# SmartChess_SCH.net
KiCad netlist of a schematic drawn in Altium Designer
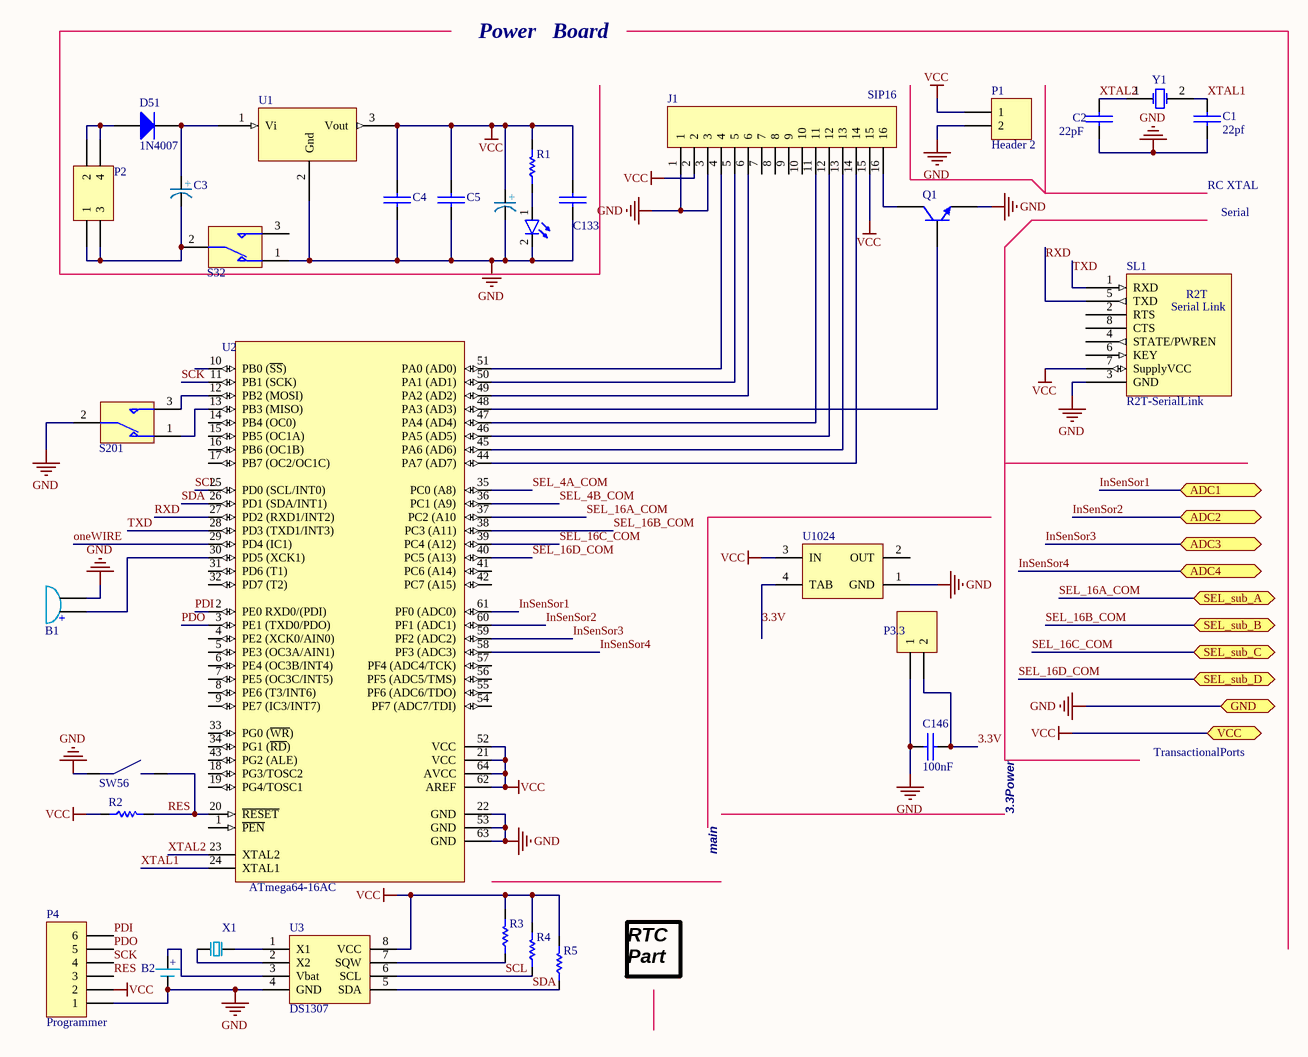
[diagram p0: SmartChess_SCH.SchDoc]

(export (version "E")
  (design (tool "Eeschema 10.0.6"))
  (components
    (comp (ref "B1")
      (value "Buzzer")
      (footprint "Buzzer")
      (fields (field (name "DESIGNER") "Hamed Jafarzadeh"))
      (libsource (lib "R2T Team Library") (part "Buzzer"))
    )
    (comp (ref "B2") (value "BAT") (footprint "BAT_H") (libsource (lib "My_lib_new") (part "BAT")))
    (comp (ref "C1")
      (value "22pf")
      (footprint "SMD_CAP_1206")
      (description "Bipolar Capacitor")
      (fields (field (name "VOLTAGE") "100V") (field (name "DESIGNER") "Saeid Jorablo"))
      (libsource (lib "My Library") (part "Cap-Bipolar"))
    )
    (comp (ref "C2")
      (value "22pF")
      (footprint "SMD_CAP_1206")
      (description "Bipolar Capacitor")
      (fields (field (name "VOLTAGE") "100V") (field (name "DESIGNER") "Saeid Jorablo"))
      (libsource (lib "My Library") (part "Cap-Bipolar"))
    )
    (comp (ref "C3")
      (value "Capacitor Polarized")
      (footprint "Electrolytic Capacitor SMD Dia-8")
      (fields (field (name "DESIGNER") "Hamed Jafarzadeh ( R2T )"))
      (libsource (lib "R2T Team Library") (part "Capacitor Polarized"))
    )
    (comp (ref "C4")
      (value "100nF")
      (footprint "SMD_CAP_1206")
      (description "Bipolar Capacitor")
      (fields (field (name "VOLTAGE") "100V") (field (name "DESIGNER") "Saeid Jorablo"))
      (libsource (lib "My Library") (part "Cap-Bipolar"))
    )
    (comp (ref "C5")
      (value "300nf")
      (footprint "SMD_CAP_1206")
      (description "Bipolar Capacitor")
      (fields (field (name "VOLTAGE") "100V") (field (name "DESIGNER") "Saeid Jorablo"))
      (libsource (lib "My Library") (part "Cap-Bipolar"))
    )
    (comp (ref "C9")
      (value "Capacitor Polarized")
      (footprint "Electrolytic Capacitor SMD Dia-8")
      (fields (field (name "DESIGNER") "Hamed Jafarzadeh ( R2T )"))
      (libsource (lib "R2T Team Library") (part "Capacitor Polarized"))
    )
    (comp (ref "C133")
      (value "100pF")
      (footprint "SMD_CAP_1206")
      (description "Bipolar Capacitor")
      (fields (field (name "VOLTAGE") "100V") (field (name "DESIGNER") "Saeid Jorablo"))
      (libsource (lib "My Library") (part "Cap-Bipolar"))
    )
    (comp (ref "C146")
      (value "100nF")
      (footprint "SMD_CAP_1206")
      (description "Bipolar Capacitor")
      (fields (field (name "VOLTAGE") "100V") (field (name "DESIGNER") "Saeid Jorablo"))
      (libsource (lib "My Library") (part "Cap-Bipolar"))
    )
    (comp (ref "D51")
      (value "1N4007")
      (footprint "My_DO-41")
      (description "1 Amp Diode")
      (libsource (lib "Mylib") (part "1N4007"))
    )
    (comp (ref "J1") (value "SIP16") (footprint "SIP16") (libsource (lib "My_lib_new") (part "SIP16")))
    (comp (ref "LED1")
      (value "Red")
      (footprint "LED SMD 1206")
      (description "LED")
      (fields (field (name "DESIGNER") "Saeid Jorablo"))
      (libsource (lib "My Library") (part "LED"))
    )
    (comp (ref "P1")
      (value "Header 2")
      (footprint "HDR1X2")
      (description "Header, 2-Pin")
      (fields (field (name "PUBLISHER") "Altium Limited"))
      (libsource (lib "") (part "Header 2_1"))
    )
    (comp (ref "P2")
      (value "Header 2X2")
      (footprint "HDR2X2")
      (description "Header, 2-Pin, Dual row")
      (fields (field (name "PUBLISHER") "Altium Limited"))
      (libsource (lib "Miscellaneous Connectors") (part "Header 2X2"))
    )
    (comp (ref "P3.3")
      (value "Header 2")
      (footprint "HDR1X2")
      (description "Header, 2-Pin")
      (fields (field (name "PUBLISHER") "Altium Limited"))
      (libsource (lib "Miscellaneous Connectors") (part "Header 2"))
    )
    (comp (ref "P4")
      (value "Programmer")
      (footprint "HDR1X6")
      (description "Header, 6-Pin")
      (fields (field (name "PUBLISHER") "Altium Limited"))
      (libsource (lib "Miscellaneous Connectors") (part "Header 6"))
    )
    (comp (ref "Q1")
      (value "C945")
      (footprint "C945")
      (description "NPN Transistor")
      (fields (field (name "DESIGNER") "Saeid Jorablo"))
      (libsource (lib "My Library") (part "C945"))
    )
    (comp (ref "R1")
      (value "330")
      (footprint "RES 0805 (2012X06L)")
      (description "Resistor")
      (fields (field (name "TOLERANCE") "5%") (field (name "POWER") "1/8 W"))
      (libsource (lib "My Library") (part "Resistor"))
    )
    (comp (ref "R2")
      (value "1K")
      (footprint "RES 0805 (2012X06L)")
      (description "Resistor")
      (fields (field (name "TOLERANCE") "5%") (field (name "POWER") "1/8 W"))
      (libsource (lib "My Library") (part "Resistor"))
    )
    (comp (ref "R3")
      (value "1K")
      (footprint "RES 0805 (2012X06L)")
      (description "Resistor")
      (fields (field (name "TOLERANCE") "5%") (field (name "POWER") "1/8 W"))
      (libsource (lib "My Library") (part "Resistor"))
    )
    (comp (ref "R4")
      (value "1K")
      (footprint "RES 0805 (2012X06L)")
      (description "Resistor")
      (fields (field (name "TOLERANCE") "5%") (field (name "POWER") "1/8 W"))
      (libsource (lib "My Library") (part "Resistor"))
    )
    (comp (ref "R5")
      (value "1K")
      (footprint "RES 0805 (2012X06L)")
      (description "Resistor")
      (fields (field (name "TOLERANCE") "5%") (field (name "POWER") "1/8 W"))
      (libsource (lib "My Library") (part "Resistor"))
    )
    (comp (ref "S32")
      (value "Switch SPDT_Subminiator")
      (footprint "SPDT Subminiator")
      (description "Subminiator SPDT Switch")
      (libsource (lib "My Library") (part "Switch SPDT_Subminiator"))
    )
    (comp (ref "S201")
      (value "Switch SPDT_Subminiator")
      (footprint "SPDT Subminiator")
      (description "Subminiator SPDT Switch")
      (libsource (lib "My Library") (part "Switch SPDT_Subminiator"))
    )
    (comp (ref "SL1")
      (value "R2T-SerialLink")
      (footprint "Bluetooth Serial")
      (fields (field (name "DESIGNER") "Hamed Jafarzadeh-WWW.R2T.IR"))
      (libsource (lib "R2T Team Library") (part "R2T-SerialLink"))
    )
    (comp (ref "SW56") (value "SWITCH") (footprint "SWITCH") (libsource (lib "SPLib") (part "SWITCH")))
    (comp (ref "U1")
      (value "78M05")
      (footprint "DPAK228P972X240-3N")
      (libsource (lib "R2T Team Library") (part "78M05"))
    )
    (comp (ref "U2")
      (value "ATmega64-16AC")
      (footprint "64A_N")
      (description "8-Bit AVR Microcontroller with 64K Bytes of In-System Programmable Flash Memory")
      (fields (field (name "PUBLISHER") "Altium Limited"))
      (libsource (lib "Atmel Microcontroller 8-Bit AVR") (part "ATmega64-16AC"))
    )
    (comp (ref "U3") (value "DS1307") (footprint "DIP8") (libsource (lib "My_lib_new") (part "DS1307")))
    (comp (ref "U1024")
      (value "LM1117IMP-x.x")
      (footprint "MP04A_N")
      (description "x.x Volt, 800mA Low-Dropout Linear Regulator, 4-pin SOT-223")
      (fields
        (field (name "PARTNUMBER") "LM1117IMP-3.3")
        (field (name "MANUFACTURER") "National Semiconductor")
        (field (name "PUBLISHER") "Altium Limited")
      )
      (libsource (lib "My Library") (part "LM1117IMP-x.x"))
    )
    (comp (ref "X1") (value "XTAL") (footprint "XTAL2") (libsource (lib "My_lib_new") (part "XTAL")))
    (comp (ref "Y1")
      (value "8Mhz")
      (footprint "Crystal SMD")
      (description "XTAL Crystal")
      (libsource (lib "My Library") (part "XTAL"))
    )
  )
  (nets
    (net (code "1") (name "/3.3V") (class "Default")
      (node (ref "C146") (pin "2") (pinfunction "-_2") (pintype "passive"))
      (node (ref "P3.3") (pin "2") (pinfunction "2_2") (pintype "passive"))
      (node (ref "U1024") (pin "4") (pinfunction "TAB_4") (pintype "power_in"))
    )
    (net (code "2") (name "/InSenSor1") (class "Default")
      (node (ref "U2") (pin "61") (pinfunction "PF0_(ADC0)_61") (pintype "bidirectional"))
    )
    (net (code "3") (name "/InSenSor2") (class "Default")
      (node (ref "U2") (pin "60") (pinfunction "PF1_(ADC1)_60") (pintype "bidirectional"))
    )
    (net (code "4") (name "/InSenSor3") (class "Default")
      (node (ref "U2") (pin "59") (pinfunction "PF2_(ADC2)_59") (pintype "bidirectional"))
    )
    (net (code "5") (name "/InSenSor4") (class "Default")
      (node (ref "U2") (pin "58") (pinfunction "PF3_(ADC3)_58") (pintype "bidirectional"))
    )
    (net (code "6") (name "/PDI") (class "Default")
      (node (ref "P4") (pin "6") (pinfunction "6_6") (pintype "passive"))
      (node (ref "U2") (pin "2") (pinfunction "PE0_RXD0/(PDI)_2") (pintype "bidirectional"))
    )
    (net (code "7") (name "/PDO") (class "Default")
      (node (ref "P4") (pin "5") (pinfunction "5_5") (pintype "passive"))
      (node (ref "U2") (pin "3") (pinfunction "PE1_(TXD0/PDO)_3") (pintype "bidirectional"))
    )
    (net (code "8") (name "/RES") (class "Default")
      (node (ref "P4") (pin "3") (pinfunction "3_3") (pintype "passive"))
      (node (ref "R2") (pin "2") (pinfunction "2_2") (pintype "passive"))
      (node (ref "SW56") (pin "2") (pinfunction "2_2") (pintype "passive"))
      (node (ref "U2") (pin "20") (pinfunction "~{RESET}_20") (pintype "input"))
    )
    (net (code "9") (name "/RXD") (class "Default")
      (node (ref "SL1") (pin "5") (pinfunction "TXD_5") (pintype "output"))
      (node (ref "U2") (pin "27") (pinfunction "PD2_(RXD1/INT2)_27") (pintype "bidirectional"))
    )
    (net (code "10") (name "/SCK") (class "Default")
      (node (ref "P4") (pin "4") (pinfunction "4_4") (pintype "passive"))
      (node (ref "U2") (pin "11") (pinfunction "PB1_(SCK)_11") (pintype "bidirectional"))
    )
    (net (code "11") (name "/SCL") (class "Default")
      (node (ref "R4") (pin "1") (pinfunction "1_1") (pintype "passive"))
      (node (ref "U2") (pin "25") (pinfunction "PD0_(SCL/INT0)_25") (pintype "bidirectional"))
      (node (ref "U3") (pin "6") (pinfunction "SCL_6") (pintype "passive"))
    )
    (net (code "12") (name "/SDA") (class "Default")
      (node (ref "R5") (pin "1") (pinfunction "1_1") (pintype "passive"))
      (node (ref "U2") (pin "26") (pinfunction "PD1_(SDA/INT1)_26") (pintype "bidirectional"))
      (node (ref "U3") (pin "5") (pinfunction "SDA_5") (pintype "passive"))
    )
    (net (code "13") (name "/SEL_4A_COM") (class "Default")
      (node (ref "U2") (pin "35") (pinfunction "PC0_(A8)_35") (pintype "bidirectional"))
    )
    (net (code "14") (name "/SEL_4B_COM") (class "Default")
      (node (ref "U2") (pin "36") (pinfunction "PC1_(A9)_36") (pintype "bidirectional"))
    )
    (net (code "15") (name "/SEL_16A_COM") (class "Default")
      (node (ref "U2") (pin "37") (pinfunction "PC2_(A10_37") (pintype "bidirectional"))
    )
    (net (code "16") (name "/SEL_16B_COM") (class "Default")
      (node (ref "U2") (pin "38") (pinfunction "PC3_(A11)_38") (pintype "bidirectional"))
    )
    (net (code "17") (name "/SEL_16C_COM") (class "Default")
      (node (ref "U2") (pin "39") (pinfunction "PC4_(A12)_39") (pintype "bidirectional"))
    )
    (net (code "18") (name "/SEL_16D_COM") (class "Default")
      (node (ref "U2") (pin "40") (pinfunction "PC5_(A13)_40") (pintype "bidirectional"))
    )
    (net (code "19") (name "/TXD") (class "Default")
      (node (ref "SL1") (pin "1") (pinfunction "RXD_1") (pintype "input"))
      (node (ref "U2") (pin "28") (pinfunction "PD3_(TXD1/INT3)_28") (pintype "bidirectional"))
    )
    (net (code "20") (name "/XTAL1") (class "Default")
      (node (ref "C1") (pin "1") (pinfunction "+_1") (pintype "passive"))
      (node (ref "U2") (pin "24") (pinfunction "XTAL1_24") (pintype "passive"))
      (node (ref "Y1") (pin "2") (pinfunction "OSC2_2") (pintype "passive"))
    )
    (net (code "21") (name "/XTAL2") (class "Default")
      (node (ref "C2") (pin "1") (pinfunction "+_1") (pintype "passive"))
      (node (ref "U2") (pin "23") (pinfunction "XTAL2_23") (pintype "passive"))
      (node (ref "Y1") (pin "1") (pinfunction "OSC1_1") (pintype "passive"))
    )
    (net (code "22") (name "/oneWIRE") (class "Default")
      (node (ref "U2") (pin "29") (pinfunction "PD4_(IC1)_29") (pintype "bidirectional"))
    )
    (net (code "23") (name "GND") (class "Default")
      (node (ref "B1") (pin "2") (pinfunction "GND_2") (pintype "passive"))
      (node (ref "B2") (pin "2") (pintype "passive"))
      (node (ref "C1") (pin "2") (pinfunction "-_2") (pintype "passive"))
      (node (ref "C133") (pin "2") (pinfunction "-_2") (pintype "passive"))
      (node (ref "C146") (pin "1") (pinfunction "+_1") (pintype "passive"))
      (node (ref "C2") (pin "2") (pinfunction "-_2") (pintype "passive"))
      (node (ref "C4") (pin "2") (pinfunction "-_2") (pintype "passive"))
      (node (ref "C5") (pin "2") (pinfunction "-_2") (pintype "passive"))
      (node (ref "C9") (pin "2") (pintype "passive"))
      (node (ref "J1") (pin "1") (pinfunction "1_1") (pintype "passive"))
      (node (ref "J1") (pin "3") (pinfunction "3_3") (pintype "passive"))
      (node (ref "LED1") (pin "2") (pinfunction "K_2") (pintype "passive"))
      (node (ref "P1") (pin "2") (pinfunction "2_2") (pintype "passive"))
      (node (ref "P3.3") (pin "1") (pinfunction "1_1") (pintype "passive"))
      (node (ref "P4") (pin "1") (pinfunction "1_1") (pintype "passive"))
      (node (ref "Q1") (pin "1") (pinfunction "E_1") (pintype "passive"))
      (node (ref "S201") (pin "2") (pinfunction "2_2") (pintype "passive"))
      (node (ref "S32") (pin "1") (pinfunction "1_1") (pintype "passive"))
      (node (ref "SL1") (pin "3") (pinfunction "GND_3") (pintype "passive"))
      (node (ref "SW56") (pin "1") (pinfunction "1_1") (pintype "passive"))
      (node (ref "U1") (pin "2") (pinfunction "Gnd_2") (pintype "passive"))
      (node (ref "U1024") (pin "1") (pinfunction "GND_1") (pintype "power_in"))
      (node (ref "U2") (pin "22") (pinfunction "GND_22") (pintype "power_in"))
      (node (ref "U2") (pin "53") (pinfunction "GND_53") (pintype "power_in"))
      (node (ref "U2") (pin "63") (pinfunction "GND_63") (pintype "power_in"))
      (node (ref "U3") (pin "4") (pinfunction "GND_4") (pintype "passive"))
    )
    (net (code "24") (name "Net-(B1-VCC)") (class "Default")
      (node (ref "B1") (pin "1") (pinfunction "VCC_1") (pintype "passive"))
      (node (ref "U2") (pin "30") (pinfunction "PD5_(XCK1)_30") (pintype "bidirectional"))
    )
    (net (code "25") (name "Net-(C3-Pad2)") (class "Default")
      (node (ref "C3") (pin "2") (pintype "passive"))
      (node (ref "P2") (pin "1") (pinfunction "1_1") (pintype "passive"))
      (node (ref "P2") (pin "3") (pinfunction "3_3") (pintype "passive"))
      (node (ref "S32") (pin "2") (pinfunction "2_2") (pintype "passive"))
    )
    (net (code "26") (name "Net-(D51-PadA)") (class "Default")
      (node (ref "D51") (pin "A") (pinfunction "A_A") (pintype "passive"))
      (node (ref "P2") (pin "2") (pinfunction "2_2") (pintype "passive"))
      (node (ref "P2") (pin "4") (pinfunction "4_4") (pintype "passive"))
    )
    (net (code "27") (name "Net-(LED1-A)") (class "Default")
      (node (ref "LED1") (pin "1") (pinfunction "A_1") (pintype "passive"))
      (node (ref "R1") (pin "1") (pinfunction "1_1") (pintype "passive"))
    )
    (net (code "28") (name "Net-(Q1-B)") (class "Default")
      (node (ref "Q1") (pin "3") (pinfunction "B_3") (pintype "passive"))
      (node (ref "U2") (pin "48") (pinfunction "PA3_(AD3)_48") (pintype "bidirectional"))
    )
    (net (code "29") (name "Net-(Q1-C)") (class "Default")
      (node (ref "J1") (pin "16") (pinfunction "16_16") (pintype "passive"))
      (node (ref "Q1") (pin "2") (pinfunction "C_2") (pintype "passive"))
    )
    (net (code "30") (name "Net-(U1-Vi)") (class "Default")
      (node (ref "C3") (pin "1") (pintype "passive"))
      (node (ref "D51") (pin "K") (pinfunction "K_K") (pintype "passive"))
      (node (ref "U1") (pin "1") (pinfunction "Vi_1") (pintype "input"))
    )
    (net (code "31") (name "Net-(U2-PA0_(AD0))") (class "Default")
      (node (ref "J1") (pin "4") (pinfunction "4_4") (pintype "passive"))
      (node (ref "U2") (pin "51") (pinfunction "PA0_(AD0)_51") (pintype "bidirectional"))
    )
    (net (code "32") (name "Net-(U2-PA1_(AD1))") (class "Default")
      (node (ref "J1") (pin "5") (pinfunction "5_5") (pintype "passive"))
      (node (ref "U2") (pin "50") (pinfunction "PA1_(AD1)_50") (pintype "bidirectional"))
    )
    (net (code "33") (name "Net-(U2-PA2_(AD2))") (class "Default")
      (node (ref "J1") (pin "6") (pinfunction "6_6") (pintype "passive"))
      (node (ref "U2") (pin "49") (pinfunction "PA2_(AD2)_49") (pintype "bidirectional"))
    )
    (net (code "34") (name "Net-(U2-PA4_(AD4))") (class "Default")
      (node (ref "J1") (pin "11") (pinfunction "11_11") (pintype "passive"))
      (node (ref "U2") (pin "47") (pinfunction "PA4_(AD4)_47") (pintype "bidirectional"))
    )
    (net (code "35") (name "Net-(U2-PA5_(AD5))") (class "Default")
      (node (ref "J1") (pin "12") (pinfunction "12_12") (pintype "passive"))
      (node (ref "U2") (pin "46") (pinfunction "PA5_(AD5)_46") (pintype "bidirectional"))
    )
    (net (code "36") (name "Net-(U2-PA6_(AD6))") (class "Default")
      (node (ref "J1") (pin "13") (pinfunction "13_13") (pintype "passive"))
      (node (ref "U2") (pin "45") (pinfunction "PA6_(AD6)_45") (pintype "bidirectional"))
    )
    (net (code "37") (name "Net-(U2-PA7_(AD7))") (class "Default")
      (node (ref "J1") (pin "14") (pinfunction "14_14") (pintype "passive"))
      (node (ref "U2") (pin "44") (pinfunction "PA7_(AD7)_44") (pintype "bidirectional"))
    )
    (net (code "38") (name "Net-(U2-PB2_(MOSI))") (class "Default")
      (node (ref "S201") (pin "3") (pinfunction "3_3") (pintype "passive"))
      (node (ref "U2") (pin "12") (pinfunction "PB2_(MOSI)_12") (pintype "bidirectional"))
    )
    (net (code "39") (name "Net-(U2-PB3_(MISO))") (class "Default")
      (node (ref "S201") (pin "1") (pinfunction "1_1") (pintype "passive"))
      (node (ref "U2") (pin "13") (pinfunction "PB3_(MISO)_13") (pintype "bidirectional"))
    )
    (net (code "40") (name "Net-(U3-SQW)") (class "Default")
      (node (ref "R3") (pin "1") (pinfunction "1_1") (pintype "passive"))
      (node (ref "U3") (pin "7") (pinfunction "SQW_7") (pintype "passive"))
    )
    (net (code "41") (name "Net-(U3-Vbat)") (class "Default")
      (node (ref "B2") (pin "1") (pintype "passive"))
      (node (ref "U3") (pin "3") (pinfunction "Vbat_3") (pintype "passive"))
    )
    (net (code "42") (name "Net-(U3-X1)") (class "Default")
      (node (ref "U3") (pin "1") (pinfunction "X1_1") (pintype "passive"))
      (node (ref "X1") (pin "1") (pintype "passive"))
    )
    (net (code "43") (name "Net-(U3-X2)") (class "Default")
      (node (ref "U3") (pin "2") (pinfunction "X2_2") (pintype "passive"))
      (node (ref "X1") (pin "2") (pintype "passive"))
    )
    (net (code "44") (name "VCC") (class "Default")
      (node (ref "C133") (pin "1") (pinfunction "+_1") (pintype "passive"))
      (node (ref "C4") (pin "1") (pinfunction "+_1") (pintype "passive"))
      (node (ref "C5") (pin "1") (pinfunction "+_1") (pintype "passive"))
      (node (ref "C9") (pin "1") (pintype "passive"))
      (node (ref "J1") (pin "15") (pinfunction "15_15") (pintype "passive"))
      (node (ref "J1") (pin "2") (pinfunction "2_2") (pintype "passive"))
      (node (ref "P1") (pin "1") (pinfunction "1_1") (pintype "passive"))
      (node (ref "P4") (pin "2") (pinfunction "2_2") (pintype "passive"))
      (node (ref "R1") (pin "2") (pinfunction "2_2") (pintype "passive"))
      (node (ref "R2") (pin "1") (pinfunction "1_1") (pintype "passive"))
      (node (ref "R3") (pin "2") (pinfunction "2_2") (pintype "passive"))
      (node (ref "R4") (pin "2") (pinfunction "2_2") (pintype "passive"))
      (node (ref "R5") (pin "2") (pinfunction "2_2") (pintype "passive"))
      (node (ref "SL1") (pin "7") (pinfunction "SupplyVCC_7") (pintype "bidirectional"))
      (node (ref "U1") (pin "3") (pinfunction "Vout_3") (pintype "output"))
      (node (ref "U1024") (pin "3") (pinfunction "IN_3") (pintype "power_in"))
      (node (ref "U2") (pin "21") (pinfunction "VCC_21") (pintype "power_in"))
      (node (ref "U2") (pin "52") (pinfunction "VCC_52") (pintype "power_in"))
      (node (ref "U2") (pin "62") (pinfunction "AREF_62") (pintype "passive"))
      (node (ref "U2") (pin "64") (pinfunction "AVCC_64") (pintype "power_in"))
      (node (ref "U3") (pin "8") (pinfunction "VCC_8") (pintype "passive"))
    )
    (net (code "45") (name "unconnected-(J1-Pad7)") (class "Default")
      (node (ref "J1") (pin "7") (pinfunction "7_7") (pintype "passive"))
    )
    (net (code "46") (name "unconnected-(J1-Pad8)") (class "Default")
      (node (ref "J1") (pin "8") (pinfunction "8_8") (pintype "passive"))
    )
    (net (code "47") (name "unconnected-(J1-Pad9)") (class "Default")
      (node (ref "J1") (pin "9") (pinfunction "9_9") (pintype "passive"))
    )
    (net (code "48") (name "unconnected-(J1-Pad10)") (class "Default")
      (node (ref "J1") (pin "10") (pinfunction "10_10") (pintype "passive"))
    )
    (net (code "49") (name "unconnected-(S32-Pad3)") (class "Default")
      (node (ref "S32") (pin "3") (pinfunction "3_3") (pintype "passive"))
    )
    (net (code "50") (name "unconnected-(SL1-CTS-Pad8)") (class "Default")
      (node (ref "SL1") (pin "8") (pinfunction "CTS_8") (pintype "passive"))
    )
    (net (code "51") (name "unconnected-(SL1-KEY-Pad6)") (class "Default")
      (node (ref "SL1") (pin "6") (pinfunction "KEY_6") (pintype "input"))
    )
    (net (code "52") (name "unconnected-(SL1-RTS-Pad2)") (class "Default")
      (node (ref "SL1") (pin "2") (pinfunction "RTS_2") (pintype "passive"))
    )
    (net (code "53") (name "unconnected-(SL1-STATE{slash}PWREN-Pad4)") (class "Default")
      (node (ref "SL1") (pin "4") (pinfunction "STATE/PWREN_4") (pintype "output"))
    )
    (net (code "54") (name "unconnected-(U2-PB0_(~{SS})-Pad10)") (class "Default")
      (node (ref "U2") (pin "10") (pinfunction "PB0_(~{SS})_10") (pintype "bidirectional"))
    )
    (net (code "55") (name "unconnected-(U2-PB4_(OC0)-Pad14)") (class "Default")
      (node (ref "U2") (pin "14") (pinfunction "PB4_(OC0)_14") (pintype "bidirectional"))
    )
    (net (code "56") (name "unconnected-(U2-PB5_(OC1A)-Pad15)") (class "Default")
      (node (ref "U2") (pin "15") (pinfunction "PB5_(OC1A)_15") (pintype "bidirectional"))
    )
    (net (code "57") (name "unconnected-(U2-PB6_(OC1B)-Pad16)") (class "Default")
      (node (ref "U2") (pin "16") (pinfunction "PB6_(OC1B)_16") (pintype "bidirectional"))
    )
    (net (code "58") (name "unconnected-(U2-PB7_(OC2{slash}OC1C)-Pad17)") (class "Default")
      (node (ref "U2") (pin "17") (pinfunction "PB7_(OC2/OC1C)_17") (pintype "bidirectional"))
    )
    (net (code "59") (name "unconnected-(U2-PC6_(A14)-Pad41)") (class "Default")
      (node (ref "U2") (pin "41") (pinfunction "PC6_(A14)_41") (pintype "bidirectional"))
    )
    (net (code "60") (name "unconnected-(U2-PC7_(A15)-Pad42)") (class "Default")
      (node (ref "U2") (pin "42") (pinfunction "PC7_(A15)_42") (pintype "bidirectional"))
    )
    (net (code "61") (name "unconnected-(U2-PD6_(T1)-Pad31)") (class "Default")
      (node (ref "U2") (pin "31") (pinfunction "PD6_(T1)_31") (pintype "bidirectional"))
    )
    (net (code "62") (name "unconnected-(U2-PD7_(T2)-Pad32)") (class "Default")
      (node (ref "U2") (pin "32") (pinfunction "PD7_(T2)_32") (pintype "bidirectional"))
    )
    (net (code "63") (name "unconnected-(U2-PE2_(XCK0{slash}AIN0)-Pad4)") (class "Default")
      (node (ref "U2") (pin "4") (pinfunction "PE2_(XCK0/AIN0)_4") (pintype "bidirectional"))
    )
    (net (code "64") (name "unconnected-(U2-PE3_(OC3A{slash}AIN1)-Pad5)") (class "Default")
      (node (ref "U2") (pin "5") (pinfunction "PE3_(OC3A/AIN1)_5") (pintype "bidirectional"))
    )
    (net (code "65") (name "unconnected-(U2-PE4_(OC3B{slash}INT4)-Pad6)") (class "Default")
      (node (ref "U2") (pin "6") (pinfunction "PE4_(OC3B/INT4)_6") (pintype "bidirectional"))
    )
    (net (code "66") (name "unconnected-(U2-PE5_(OC3C{slash}INT5)-Pad7)") (class "Default")
      (node (ref "U2") (pin "7") (pinfunction "PE5_(OC3C/INT5)_7") (pintype "bidirectional"))
    )
    (net (code "67") (name "unconnected-(U2-PE6_(T3{slash}INT6)-Pad8)") (class "Default")
      (node (ref "U2") (pin "8") (pinfunction "PE6_(T3/INT6)_8") (pintype "bidirectional"))
    )
    (net (code "68") (name "unconnected-(U2-PE7_(IC3{slash}INT7)-Pad9)") (class "Default")
      (node (ref "U2") (pin "9") (pinfunction "PE7_(IC3/INT7)_9") (pintype "bidirectional"))
    )
    (net (code "69") (name "unconnected-(U2-PF4_(ADC4{slash}TCK)-Pad57)") (class "Default")
      (node (ref "U2") (pin "57") (pinfunction "PF4_(ADC4/TCK)_57") (pintype "bidirectional"))
    )
    (net (code "70") (name "unconnected-(U2-PF5_(ADC5{slash}TMS)-Pad56)") (class "Default")
      (node (ref "U2") (pin "56") (pinfunction "PF5_(ADC5/TMS)_56") (pintype "bidirectional"))
    )
    (net (code "71") (name "unconnected-(U2-PF6_(ADC6{slash}TDO)-Pad55)") (class "Default")
      (node (ref "U2") (pin "55") (pinfunction "PF6_(ADC6/TDO)_55") (pintype "bidirectional"))
    )
    (net (code "72") (name "unconnected-(U2-PF7_(ADC7{slash}TDI)-Pad54)") (class "Default")
      (node (ref "U2") (pin "54") (pinfunction "PF7_(ADC7/TDI)_54") (pintype "bidirectional"))
    )
    (net (code "73") (name "unconnected-(U2-PG0_(~{WR})-Pad33)") (class "Default")
      (node (ref "U2") (pin "33") (pinfunction "PG0_(~{WR})_33") (pintype "bidirectional"))
    )
    (net (code "74") (name "unconnected-(U2-PG1_(~{RD})-Pad34)") (class "Default")
      (node (ref "U2") (pin "34") (pinfunction "PG1_(~{RD})_34") (pintype "bidirectional"))
    )
    (net (code "75") (name "unconnected-(U2-PG2_(ALE)-Pad43)") (class "Default")
      (node (ref "U2") (pin "43") (pinfunction "PG2_(ALE)_43") (pintype "bidirectional"))
    )
    (net (code "76") (name "unconnected-(U2-PG3{slash}TOSC2-Pad18)") (class "Default")
      (node (ref "U2") (pin "18") (pinfunction "PG3/TOSC2_18") (pintype "bidirectional"))
    )
    (net (code "77") (name "unconnected-(U2-PG4{slash}TOSC1-Pad19)") (class "Default")
      (node (ref "U2") (pin "19") (pinfunction "PG4/TOSC1_19") (pintype "bidirectional"))
    )
    (net (code "78") (name "unconnected-(U2-~{PEN}-Pad1)") (class "Default")
      (node (ref "U2") (pin "1") (pinfunction "~{PEN}_1") (pintype "input"))
    )
    (net (code "79") (name "unconnected-(U1024-OUT-Pad2)") (class "Default")
      (node (ref "U1024") (pin "2") (pinfunction "OUT_2") (pintype "power_in"))
    )
  )
)
